# LDAQ-MOD-IO40.net
KiCad netlist of a schematic drawn in EAGLE
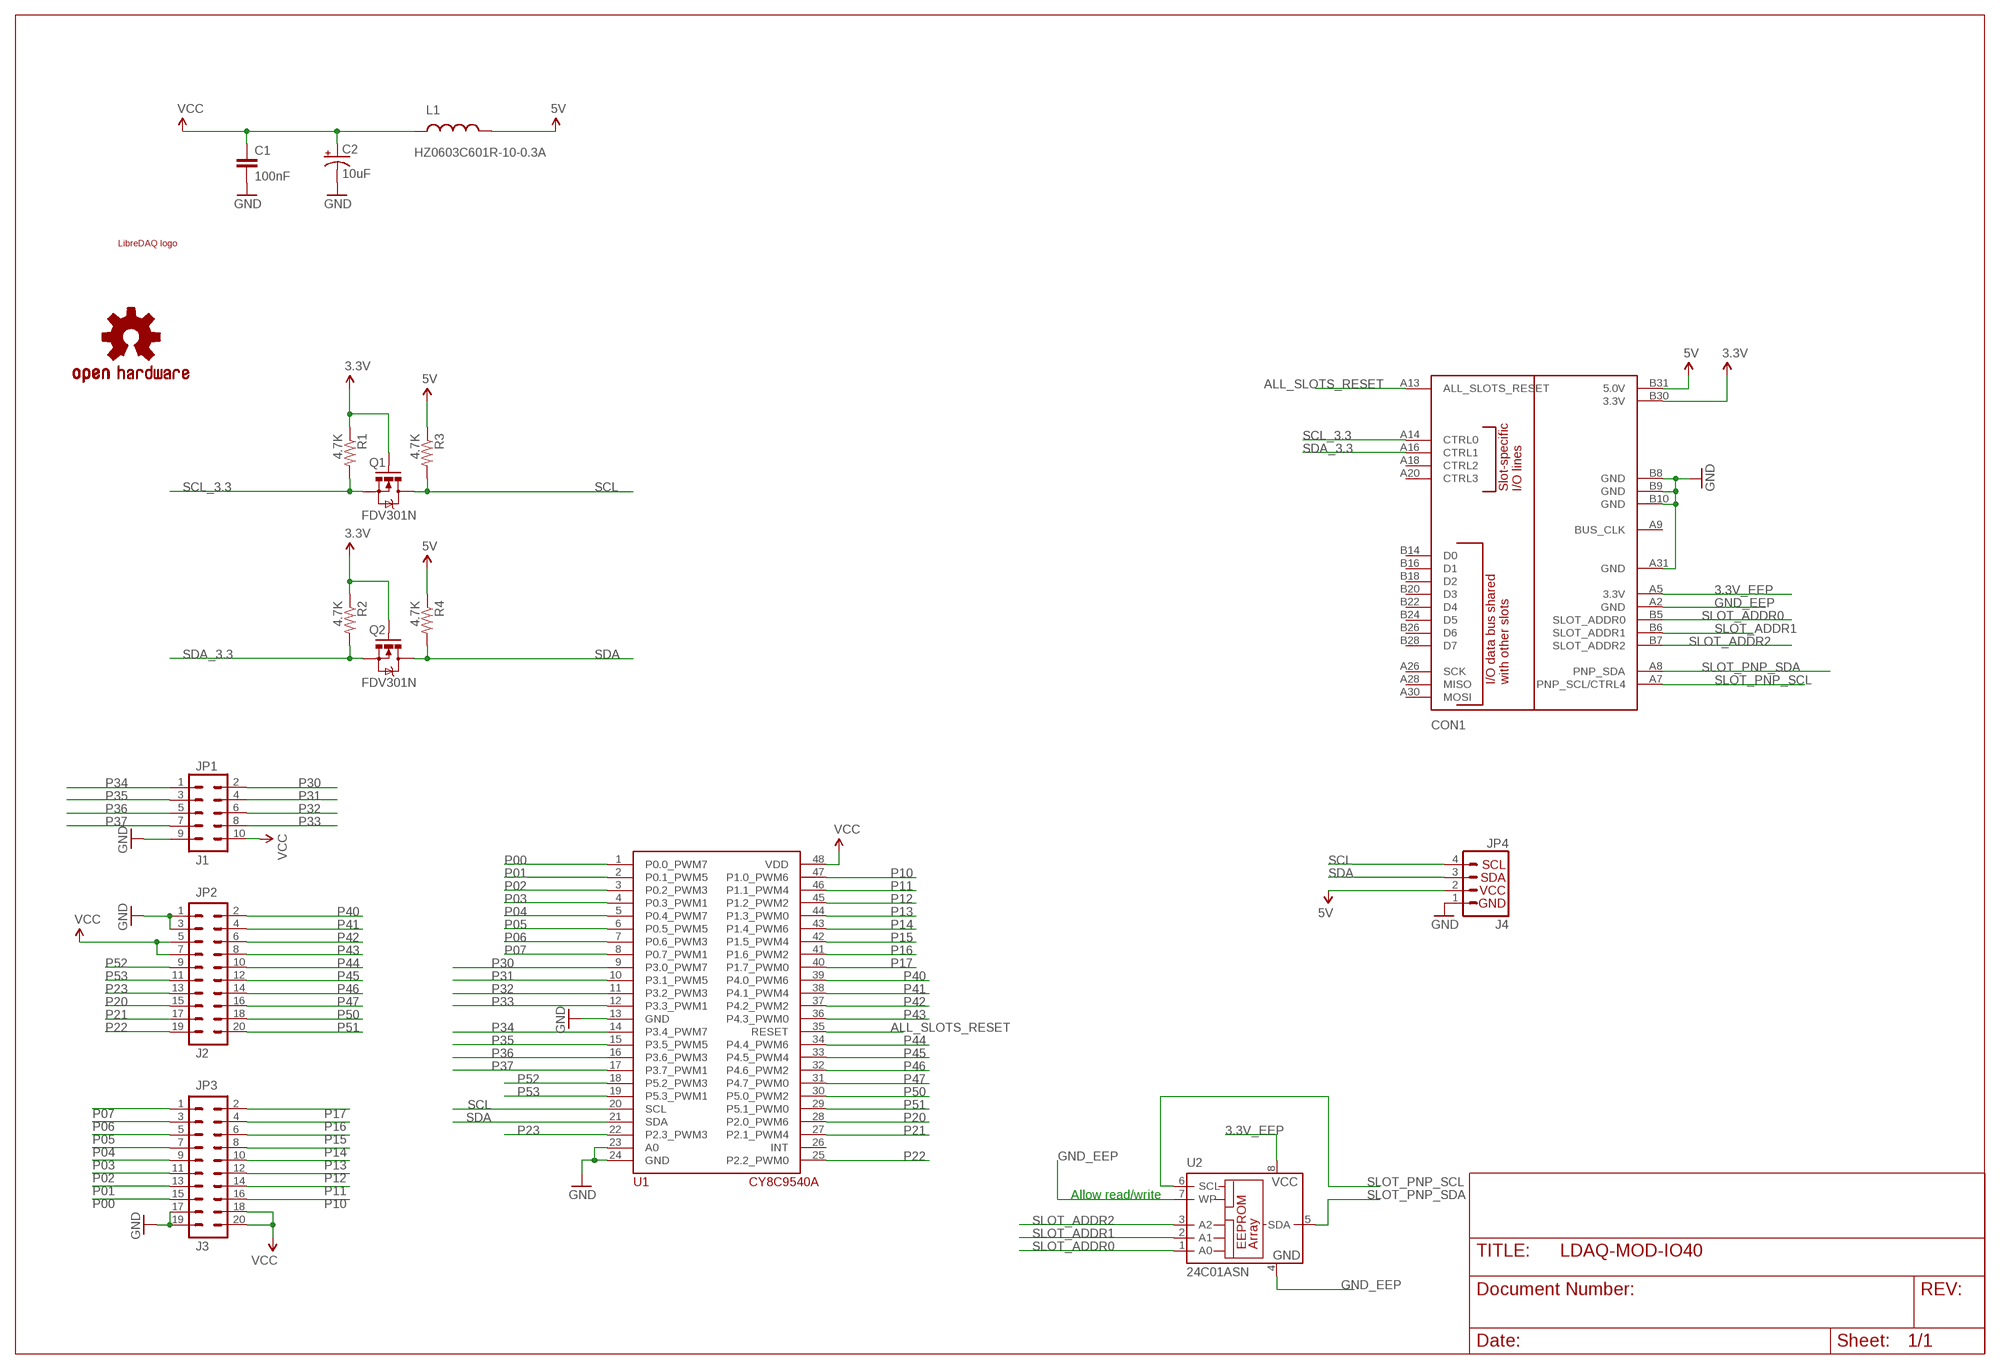
[diagram p0: schematic, sheet 1]

(export (version "E")
  (design (tool "Eeschema 10.0.6"))
  (components
    (comp (ref "C1")
      (value "100nF")
      (footprint "eagle-import:0603-CAP")
      (libsource (lib "eagle-import") (part "CAP0603-CAP"))
    )
    (comp (ref "C2")
      (value "10uF")
      (footprint "eagle-import:EIA3216")
      (libsource (lib "eagle-import") (part "CAP_POL1206"))
    )
    (comp (ref "CON1")
      (value "C1")
      (footprint "eagle-import:PCI-E_64_EDGE_70X60_PADS-ONLY")
      (libsource (lib "eagle-import") (part "LIBREDAQ_DAUGHTER_BOARDPCI-64-SIZE1-PADS"))
    )
    (comp (ref "JP1")
      (value "J1")
      (footprint "eagle-import:2X5-SHROUDED")
      (libsource (lib "eagle-import") (part "M05X2SHD"))
    )
    (comp (ref "JP2")
      (value "J2")
      (footprint "eagle-import:2X10-SHROUDED")
      (libsource (lib "eagle-import") (part "M10X22X10-SHROUDED"))
    )
    (comp (ref "JP3")
      (value "J3")
      (footprint "eagle-import:2X10-SHROUDED")
      (libsource (lib "eagle-import") (part "M10X22X10-SHROUDED"))
    )
    (comp (ref "JP4")
      (value "J4")
      (footprint "eagle-import:1X04")
      (libsource (lib "eagle-import") (part "I2C_STANDARD"))
    )
    (comp (ref "L1")
      (value "HZ0603C601R-10-0.3A")
      (footprint "eagle-import:0603")
      (libsource (lib "eagle-import") (part "INDUCTOR0603"))
    )
    (comp (ref "LOGO1")
      (value "LIBREDAQ_LOGO_MINILOGO_GENERIC")
      (footprint "eagle-import:LIBREDAQ_LOGO")
      (libsource (lib "eagle-import") (part "LIBREDAQ_LOGO_MINILOGO_GENERIC"))
    )
    (comp (ref "LOGO2")
      (value "OSHW-LOGOM")
      (footprint "eagle-import:OSHW-LOGO-M")
      (libsource (lib "eagle-import") (part "OSHW-LOGOM"))
    )
    (comp (ref "Q1")
      (value "FDV301N")
      (footprint "eagle-import:SOT23-3")
      (libsource (lib "eagle-import") (part "MOSFET-NCHANNELSMD"))
    )
    (comp (ref "Q2")
      (value "FDV301N")
      (footprint "eagle-import:SOT23-3")
      (libsource (lib "eagle-import") (part "MOSFET-NCHANNELSMD"))
    )
    (comp (ref "R1")
      (value "4.7K")
      (footprint "eagle-import:0603-RES")
      (libsource (lib "eagle-import") (part "RESISTOR0603-RES"))
    )
    (comp (ref "R2")
      (value "4.7K")
      (footprint "eagle-import:0603-RES")
      (libsource (lib "eagle-import") (part "RESISTOR0603-RES"))
    )
    (comp (ref "R3")
      (value "4.7K")
      (footprint "eagle-import:0603-RES")
      (libsource (lib "eagle-import") (part "RESISTOR0603-RES"))
    )
    (comp (ref "R4")
      (value "4.7K")
      (footprint "eagle-import:0603-RES")
      (libsource (lib "eagle-import") (part "RESISTOR0603-RES"))
    )
    (comp (ref "U1")
      (value "CY8C9540A")
      (footprint "eagle-import:SSOP-48")
      (libsource (lib "eagle-import") (part "CY8C9540A"))
    )
    (comp (ref "U2")
      (value "24C01ASN")
      (footprint "eagle-import:SO-08")
      (fields (field (name "MPN") "AT24C01BN-SH-B"))
      (libsource (lib "eagle-import") (part "24CSN01A"))
    )
  )
  (nets
    (net (code "1") (name "/3.3V_EEP") (class "Default")
      (node (ref "CON1") (pin "A5") (pinfunction "3.3V_A5") (pintype "bidirectional"))
      (node (ref "U2") (pin "8") (pinfunction "VCC_8") (pintype "power_in"))
    )
    (net (code "2") (name "/ALL_SLOTS_RESET") (class "Default")
      (node (ref "CON1") (pin "A13") (pinfunction "ALL_SLOTS_RESET_A13") (pintype "bidirectional"))
      (node (ref "U1") (pin "35") (pinfunction "RESET_35") (pintype "bidirectional"))
    )
    (net (code "3") (name "/GND_EEP") (class "Default")
      (node (ref "CON1") (pin "A2") (pinfunction "GND_A2") (pintype "bidirectional"))
      (node (ref "U2") (pin "4") (pinfunction "GND_4") (pintype "power_in"))
      (node (ref "U2") (pin "7") (pinfunction "WP_7") (pintype "input"))
    )
    (net (code "4") (name "/P00") (class "Default")
      (node (ref "JP3") (pin "15") (pinfunction "15_15") (pintype "passive"))
      (node (ref "U1") (pin "1") (pinfunction "P0.0_PWM7_1") (pintype "bidirectional"))
    )
    (net (code "5") (name "/P01") (class "Default")
      (node (ref "JP3") (pin "13") (pinfunction "13_13") (pintype "passive"))
      (node (ref "U1") (pin "2") (pinfunction "P0.1_PWM5_2") (pintype "bidirectional"))
    )
    (net (code "6") (name "/P02") (class "Default")
      (node (ref "JP3") (pin "11") (pinfunction "11_11") (pintype "passive"))
      (node (ref "U1") (pin "3") (pinfunction "P0.2_PWM3_3") (pintype "bidirectional"))
    )
    (net (code "7") (name "/P03") (class "Default")
      (node (ref "JP3") (pin "9") (pinfunction "9_9") (pintype "passive"))
      (node (ref "U1") (pin "4") (pinfunction "P0.3_PWM1_4") (pintype "bidirectional"))
    )
    (net (code "8") (name "/P04") (class "Default")
      (node (ref "JP3") (pin "7") (pinfunction "7_7") (pintype "passive"))
      (node (ref "U1") (pin "5") (pinfunction "P0.4_PWM7_5") (pintype "bidirectional"))
    )
    (net (code "9") (name "/P05") (class "Default")
      (node (ref "JP3") (pin "5") (pinfunction "5_5") (pintype "passive"))
      (node (ref "U1") (pin "6") (pinfunction "P0.5_PWM5_6") (pintype "bidirectional"))
    )
    (net (code "10") (name "/P06") (class "Default")
      (node (ref "JP3") (pin "3") (pinfunction "3_3") (pintype "passive"))
      (node (ref "U1") (pin "7") (pinfunction "P0.6_PWM3_7") (pintype "bidirectional"))
    )
    (net (code "11") (name "/P07") (class "Default")
      (node (ref "JP3") (pin "1") (pinfunction "1_1") (pintype "passive"))
      (node (ref "U1") (pin "8") (pinfunction "P0.7_PWM1_8") (pintype "bidirectional"))
    )
    (net (code "12") (name "/P10") (class "Default")
      (node (ref "JP3") (pin "16") (pinfunction "16_16") (pintype "passive"))
      (node (ref "U1") (pin "47") (pinfunction "P1.0_PWM6_47") (pintype "bidirectional"))
    )
    (net (code "13") (name "/P11") (class "Default")
      (node (ref "JP3") (pin "14") (pinfunction "14_14") (pintype "passive"))
      (node (ref "U1") (pin "46") (pinfunction "P1.1_PWM4_46") (pintype "bidirectional"))
    )
    (net (code "14") (name "/P12") (class "Default")
      (node (ref "JP3") (pin "12") (pinfunction "12_12") (pintype "passive"))
      (node (ref "U1") (pin "45") (pinfunction "P1.2_PWM2_45") (pintype "bidirectional"))
    )
    (net (code "15") (name "/P13") (class "Default")
      (node (ref "JP3") (pin "10") (pinfunction "10_10") (pintype "passive"))
      (node (ref "U1") (pin "44") (pinfunction "P1.3_PWM0_44") (pintype "bidirectional"))
    )
    (net (code "16") (name "/P14") (class "Default")
      (node (ref "JP3") (pin "8") (pinfunction "8_8") (pintype "passive"))
      (node (ref "U1") (pin "43") (pinfunction "P1.4_PWM6_43") (pintype "bidirectional"))
    )
    (net (code "17") (name "/P15") (class "Default")
      (node (ref "JP3") (pin "6") (pinfunction "6_6") (pintype "passive"))
      (node (ref "U1") (pin "42") (pinfunction "P1.5_PWM4_42") (pintype "bidirectional"))
    )
    (net (code "18") (name "/P16") (class "Default")
      (node (ref "JP3") (pin "4") (pinfunction "4_4") (pintype "passive"))
      (node (ref "U1") (pin "41") (pinfunction "P1.6_PWM2_41") (pintype "bidirectional"))
    )
    (net (code "19") (name "/P17") (class "Default")
      (node (ref "JP3") (pin "2") (pinfunction "2_2") (pintype "passive"))
      (node (ref "U1") (pin "40") (pinfunction "P1.7_PWM0_40") (pintype "bidirectional"))
    )
    (net (code "20") (name "/P20") (class "Default")
      (node (ref "JP2") (pin "15") (pinfunction "15_15") (pintype "passive"))
      (node (ref "U1") (pin "28") (pinfunction "P2.0_PWM6_28") (pintype "bidirectional"))
    )
    (net (code "21") (name "/P21") (class "Default")
      (node (ref "JP2") (pin "17") (pinfunction "17_17") (pintype "passive"))
      (node (ref "U1") (pin "27") (pinfunction "P2.1_PWM4_27") (pintype "bidirectional"))
    )
    (net (code "22") (name "/P22") (class "Default")
      (node (ref "JP2") (pin "19") (pinfunction "19_19") (pintype "passive"))
      (node (ref "U1") (pin "25") (pinfunction "P2.2_PWM0_25") (pintype "bidirectional"))
    )
    (net (code "23") (name "/P23") (class "Default")
      (node (ref "JP2") (pin "13") (pinfunction "13_13") (pintype "passive"))
      (node (ref "U1") (pin "22") (pinfunction "P2.3_PWM3_22") (pintype "bidirectional"))
    )
    (net (code "24") (name "/P30") (class "Default")
      (node (ref "JP1") (pin "2") (pinfunction "2_2") (pintype "passive"))
      (node (ref "U1") (pin "9") (pinfunction "P3.0_PWM7_9") (pintype "bidirectional"))
    )
    (net (code "25") (name "/P31") (class "Default")
      (node (ref "JP1") (pin "4") (pinfunction "4_4") (pintype "passive"))
      (node (ref "U1") (pin "10") (pinfunction "P3.1_PWM5_10") (pintype "bidirectional"))
    )
    (net (code "26") (name "/P32") (class "Default")
      (node (ref "JP1") (pin "6") (pinfunction "6_6") (pintype "passive"))
      (node (ref "U1") (pin "11") (pinfunction "P3.2_PWM3_11") (pintype "bidirectional"))
    )
    (net (code "27") (name "/P33") (class "Default")
      (node (ref "JP1") (pin "8") (pinfunction "8_8") (pintype "passive"))
      (node (ref "U1") (pin "12") (pinfunction "P3.3_PWM1_12") (pintype "bidirectional"))
    )
    (net (code "28") (name "/P34") (class "Default")
      (node (ref "JP1") (pin "1") (pinfunction "1_1") (pintype "passive"))
      (node (ref "U1") (pin "14") (pinfunction "P3.4_PWM7_14") (pintype "bidirectional"))
    )
    (net (code "29") (name "/P35") (class "Default")
      (node (ref "JP1") (pin "3") (pinfunction "3_3") (pintype "passive"))
      (node (ref "U1") (pin "15") (pinfunction "P3.5_PWM5_15") (pintype "bidirectional"))
    )
    (net (code "30") (name "/P36") (class "Default")
      (node (ref "JP1") (pin "5") (pinfunction "5_5") (pintype "passive"))
      (node (ref "U1") (pin "16") (pinfunction "P3.6_PWM3_16") (pintype "bidirectional"))
    )
    (net (code "31") (name "/P37") (class "Default")
      (node (ref "JP1") (pin "7") (pinfunction "7_7") (pintype "passive"))
      (node (ref "U1") (pin "17") (pinfunction "P3.7_PWM1_17") (pintype "bidirectional"))
    )
    (net (code "32") (name "/P40") (class "Default")
      (node (ref "JP2") (pin "2") (pinfunction "2_2") (pintype "passive"))
      (node (ref "U1") (pin "39") (pinfunction "P4.0_PWM6_39") (pintype "bidirectional"))
    )
    (net (code "33") (name "/P41") (class "Default")
      (node (ref "JP2") (pin "4") (pinfunction "4_4") (pintype "passive"))
      (node (ref "U1") (pin "38") (pinfunction "P4.1_PWM4_38") (pintype "bidirectional"))
    )
    (net (code "34") (name "/P42") (class "Default")
      (node (ref "JP2") (pin "6") (pinfunction "6_6") (pintype "passive"))
      (node (ref "U1") (pin "37") (pinfunction "P4.2_PWM2_37") (pintype "bidirectional"))
    )
    (net (code "35") (name "/P43") (class "Default")
      (node (ref "JP2") (pin "8") (pinfunction "8_8") (pintype "passive"))
      (node (ref "U1") (pin "36") (pinfunction "P4.3_PWM0_36") (pintype "bidirectional"))
    )
    (net (code "36") (name "/P44") (class "Default")
      (node (ref "JP2") (pin "10") (pinfunction "10_10") (pintype "passive"))
      (node (ref "U1") (pin "34") (pinfunction "P4.4_PWM6_34") (pintype "bidirectional"))
    )
    (net (code "37") (name "/P45") (class "Default")
      (node (ref "JP2") (pin "12") (pinfunction "12_12") (pintype "passive"))
      (node (ref "U1") (pin "33") (pinfunction "P4.5_PWM4_33") (pintype "bidirectional"))
    )
    (net (code "38") (name "/P46") (class "Default")
      (node (ref "JP2") (pin "14") (pinfunction "14_14") (pintype "passive"))
      (node (ref "U1") (pin "32") (pinfunction "P4.6_PWM2_32") (pintype "bidirectional"))
    )
    (net (code "39") (name "/P47") (class "Default")
      (node (ref "JP2") (pin "16") (pinfunction "16_16") (pintype "passive"))
      (node (ref "U1") (pin "31") (pinfunction "P4.7_PWM0_31") (pintype "bidirectional"))
    )
    (net (code "40") (name "/P50") (class "Default")
      (node (ref "JP2") (pin "18") (pinfunction "18_18") (pintype "passive"))
      (node (ref "U1") (pin "30") (pinfunction "P5.0_PWM2_30") (pintype "bidirectional"))
    )
    (net (code "41") (name "/P51") (class "Default")
      (node (ref "JP2") (pin "20") (pinfunction "20_20") (pintype "passive"))
      (node (ref "U1") (pin "29") (pinfunction "P5.1_PWM0_29") (pintype "bidirectional"))
    )
    (net (code "42") (name "/P52") (class "Default")
      (node (ref "JP2") (pin "9") (pinfunction "9_9") (pintype "passive"))
      (node (ref "U1") (pin "18") (pinfunction "P5.2_PWM3_18") (pintype "bidirectional"))
    )
    (net (code "43") (name "/P53") (class "Default")
      (node (ref "JP2") (pin "11") (pinfunction "11_11") (pintype "passive"))
      (node (ref "U1") (pin "19") (pinfunction "P5.3_PWM1_19") (pintype "bidirectional"))
    )
    (net (code "44") (name "/SCL") (class "Default")
      (node (ref "JP4") (pin "4") (pinfunction "4_4") (pintype "passive"))
      (node (ref "Q1") (pin "3") (pinfunction "D_3") (pintype "passive"))
      (node (ref "R3") (pin "2") (pinfunction "2_2") (pintype "passive"))
      (node (ref "U1") (pin "20") (pinfunction "SCL_20") (pintype "bidirectional"))
    )
    (net (code "45") (name "/SCL_3.3") (class "Default")
      (node (ref "CON1") (pin "A14") (pinfunction "CTRL0_A14") (pintype "bidirectional"))
      (node (ref "Q1") (pin "2") (pinfunction "S_2") (pintype "passive"))
      (node (ref "R1") (pin "2") (pinfunction "2_2") (pintype "passive"))
    )
    (net (code "46") (name "/SDA") (class "Default")
      (node (ref "JP4") (pin "3") (pinfunction "3_3") (pintype "passive"))
      (node (ref "Q2") (pin "3") (pinfunction "D_3") (pintype "passive"))
      (node (ref "R4") (pin "2") (pinfunction "2_2") (pintype "passive"))
      (node (ref "U1") (pin "21") (pinfunction "SDA_21") (pintype "bidirectional"))
    )
    (net (code "47") (name "/SDA_3.3") (class "Default")
      (node (ref "CON1") (pin "A16") (pinfunction "CTRL1_A16") (pintype "bidirectional"))
      (node (ref "Q2") (pin "2") (pinfunction "S_2") (pintype "passive"))
      (node (ref "R2") (pin "2") (pinfunction "2_2") (pintype "passive"))
    )
    (net (code "48") (name "/SLOT_ADDR0") (class "Default")
      (node (ref "CON1") (pin "B5") (pinfunction "SLOT_ADDR0_B5") (pintype "bidirectional"))
      (node (ref "U2") (pin "1") (pinfunction "A0_1") (pintype "input"))
    )
    (net (code "49") (name "/SLOT_ADDR1") (class "Default")
      (node (ref "CON1") (pin "B6") (pinfunction "SLOT_ADDR1_B6") (pintype "bidirectional"))
      (node (ref "U2") (pin "2") (pinfunction "A1_2") (pintype "input"))
    )
    (net (code "50") (name "/SLOT_ADDR2") (class "Default")
      (node (ref "CON1") (pin "B7") (pinfunction "SLOT_ADDR2_B7") (pintype "bidirectional"))
      (node (ref "U2") (pin "3") (pinfunction "A2_3") (pintype "input"))
    )
    (net (code "51") (name "/SLOT_PNP_SCL") (class "Default")
      (node (ref "CON1") (pin "A7") (pinfunction "PNP_SCL/CTRL4_A7") (pintype "bidirectional"))
      (node (ref "U2") (pin "6") (pinfunction "SCL_6") (pintype "input"))
    )
    (net (code "52") (name "/SLOT_PNP_SDA") (class "Default")
      (node (ref "CON1") (pin "A8") (pinfunction "PNP_SDA_A8") (pintype "bidirectional"))
      (node (ref "U2") (pin "5") (pinfunction "SDA_5") (pintype "bidirectional"))
    )
    (net (code "53") (name "3.3V") (class "Default")
      (node (ref "CON1") (pin "B30") (pinfunction "3.3V_B30") (pintype "bidirectional"))
      (node (ref "Q1") (pin "1") (pinfunction "G_1") (pintype "passive"))
      (node (ref "Q2") (pin "1") (pinfunction "G_1") (pintype "passive"))
      (node (ref "R1") (pin "1") (pinfunction "1_1") (pintype "passive"))
      (node (ref "R2") (pin "1") (pinfunction "1_1") (pintype "passive"))
    )
    (net (code "54") (name "5V") (class "Default")
      (node (ref "CON1") (pin "B31") (pinfunction "5.0V_B31") (pintype "bidirectional"))
      (node (ref "JP4") (pin "2") (pinfunction "2_2") (pintype "passive"))
      (node (ref "L1") (pin "2") (pinfunction "2_2") (pintype "passive"))
      (node (ref "R3") (pin "1") (pinfunction "1_1") (pintype "passive"))
      (node (ref "R4") (pin "1") (pinfunction "1_1") (pintype "passive"))
    )
    (net (code "55") (name "GND") (class "Default")
      (node (ref "C1") (pin "2") (pinfunction "2_2") (pintype "passive"))
      (node (ref "C2") (pin "C") (pinfunction "-_C") (pintype "passive"))
      (node (ref "CON1") (pin "A31") (pinfunction "GND_A31") (pintype "bidirectional"))
      (node (ref "CON1") (pin "B10") (pinfunction "GND_B10") (pintype "bidirectional"))
      (node (ref "CON1") (pin "B8") (pinfunction "GND_B8") (pintype "bidirectional"))
      (node (ref "CON1") (pin "B9") (pinfunction "GND_B9") (pintype "bidirectional"))
      (node (ref "JP1") (pin "9") (pinfunction "9_9") (pintype "passive"))
      (node (ref "JP2") (pin "1") (pinfunction "1_1") (pintype "passive"))
      (node (ref "JP2") (pin "3") (pinfunction "3_3") (pintype "passive"))
      (node (ref "JP3") (pin "17") (pinfunction "17_17") (pintype "passive"))
      (node (ref "JP3") (pin "19") (pinfunction "19_19") (pintype "passive"))
      (node (ref "JP4") (pin "1") (pinfunction "1_1") (pintype "passive"))
      (node (ref "U1") (pin "13") (pinfunction "GND_13") (pintype "bidirectional"))
      (node (ref "U1") (pin "23") (pinfunction "A0_23") (pintype "bidirectional"))
      (node (ref "U1") (pin "24") (pinfunction "GND_24") (pintype "bidirectional"))
    )
    (net (code "56") (name "VCC") (class "Default")
      (node (ref "C1") (pin "1") (pinfunction "1_1") (pintype "passive"))
      (node (ref "C2") (pin "A") (pinfunction "+_A") (pintype "passive"))
      (node (ref "JP1") (pin "10") (pinfunction "10_10") (pintype "passive"))
      (node (ref "JP2") (pin "5") (pinfunction "5_5") (pintype "passive"))
      (node (ref "JP2") (pin "7") (pinfunction "7_7") (pintype "passive"))
      (node (ref "JP3") (pin "18") (pinfunction "18_18") (pintype "passive"))
      (node (ref "JP3") (pin "20") (pinfunction "20_20") (pintype "passive"))
      (node (ref "L1") (pin "1") (pinfunction "1_1") (pintype "passive"))
      (node (ref "U1") (pin "48") (pinfunction "VDD_48") (pintype "bidirectional"))
    )
    (net (code "57") (name "unconnected-(CON1-BUS_CLK-PadA9)") (class "Default")
      (node (ref "CON1") (pin "A9") (pinfunction "BUS_CLK_A9") (pintype "bidirectional"))
    )
    (net (code "58") (name "unconnected-(CON1-CTRL2-PadA18)") (class "Default")
      (node (ref "CON1") (pin "A18") (pinfunction "CTRL2_A18") (pintype "bidirectional"))
    )
    (net (code "59") (name "unconnected-(CON1-CTRL3-PadA20)") (class "Default")
      (node (ref "CON1") (pin "A20") (pinfunction "CTRL3_A20") (pintype "bidirectional"))
    )
    (net (code "60") (name "unconnected-(CON1-D0-PadB14)") (class "Default")
      (node (ref "CON1") (pin "B14") (pinfunction "D0_B14") (pintype "bidirectional"))
    )
    (net (code "61") (name "unconnected-(CON1-D1-PadB16)") (class "Default")
      (node (ref "CON1") (pin "B16") (pinfunction "D1_B16") (pintype "bidirectional"))
    )
    (net (code "62") (name "unconnected-(CON1-D2-PadB18)") (class "Default")
      (node (ref "CON1") (pin "B18") (pinfunction "D2_B18") (pintype "bidirectional"))
    )
    (net (code "63") (name "unconnected-(CON1-D3-PadB20)") (class "Default")
      (node (ref "CON1") (pin "B20") (pinfunction "D3_B20") (pintype "bidirectional"))
    )
    (net (code "64") (name "unconnected-(CON1-D4-PadB22)") (class "Default")
      (node (ref "CON1") (pin "B22") (pinfunction "D4_B22") (pintype "bidirectional"))
    )
    (net (code "65") (name "unconnected-(CON1-D5-PadB24)") (class "Default")
      (node (ref "CON1") (pin "B24") (pinfunction "D5_B24") (pintype "bidirectional"))
    )
    (net (code "66") (name "unconnected-(CON1-D6-PadB26)") (class "Default")
      (node (ref "CON1") (pin "B26") (pinfunction "D6_B26") (pintype "bidirectional"))
    )
    (net (code "67") (name "unconnected-(CON1-D7-PadB28)") (class "Default")
      (node (ref "CON1") (pin "B28") (pinfunction "D7_B28") (pintype "bidirectional"))
    )
    (net (code "68") (name "unconnected-(CON1-MISO-PadA28)") (class "Default")
      (node (ref "CON1") (pin "A28") (pinfunction "MISO_A28") (pintype "bidirectional"))
    )
    (net (code "69") (name "unconnected-(CON1-MOSI-PadA30)") (class "Default")
      (node (ref "CON1") (pin "A30") (pinfunction "MOSI_A30") (pintype "bidirectional"))
    )
    (net (code "70") (name "unconnected-(CON1-SCK-PadA26)") (class "Default")
      (node (ref "CON1") (pin "A26") (pinfunction "SCK_A26") (pintype "bidirectional"))
    )
    (net (code "71") (name "unconnected-(U1-INT-Pad26)") (class "Default")
      (node (ref "U1") (pin "26") (pinfunction "INT_26") (pintype "bidirectional"))
    )
  )
)
